# Sheet1.net
KiCad netlist of a schematic drawn in Altium Designer
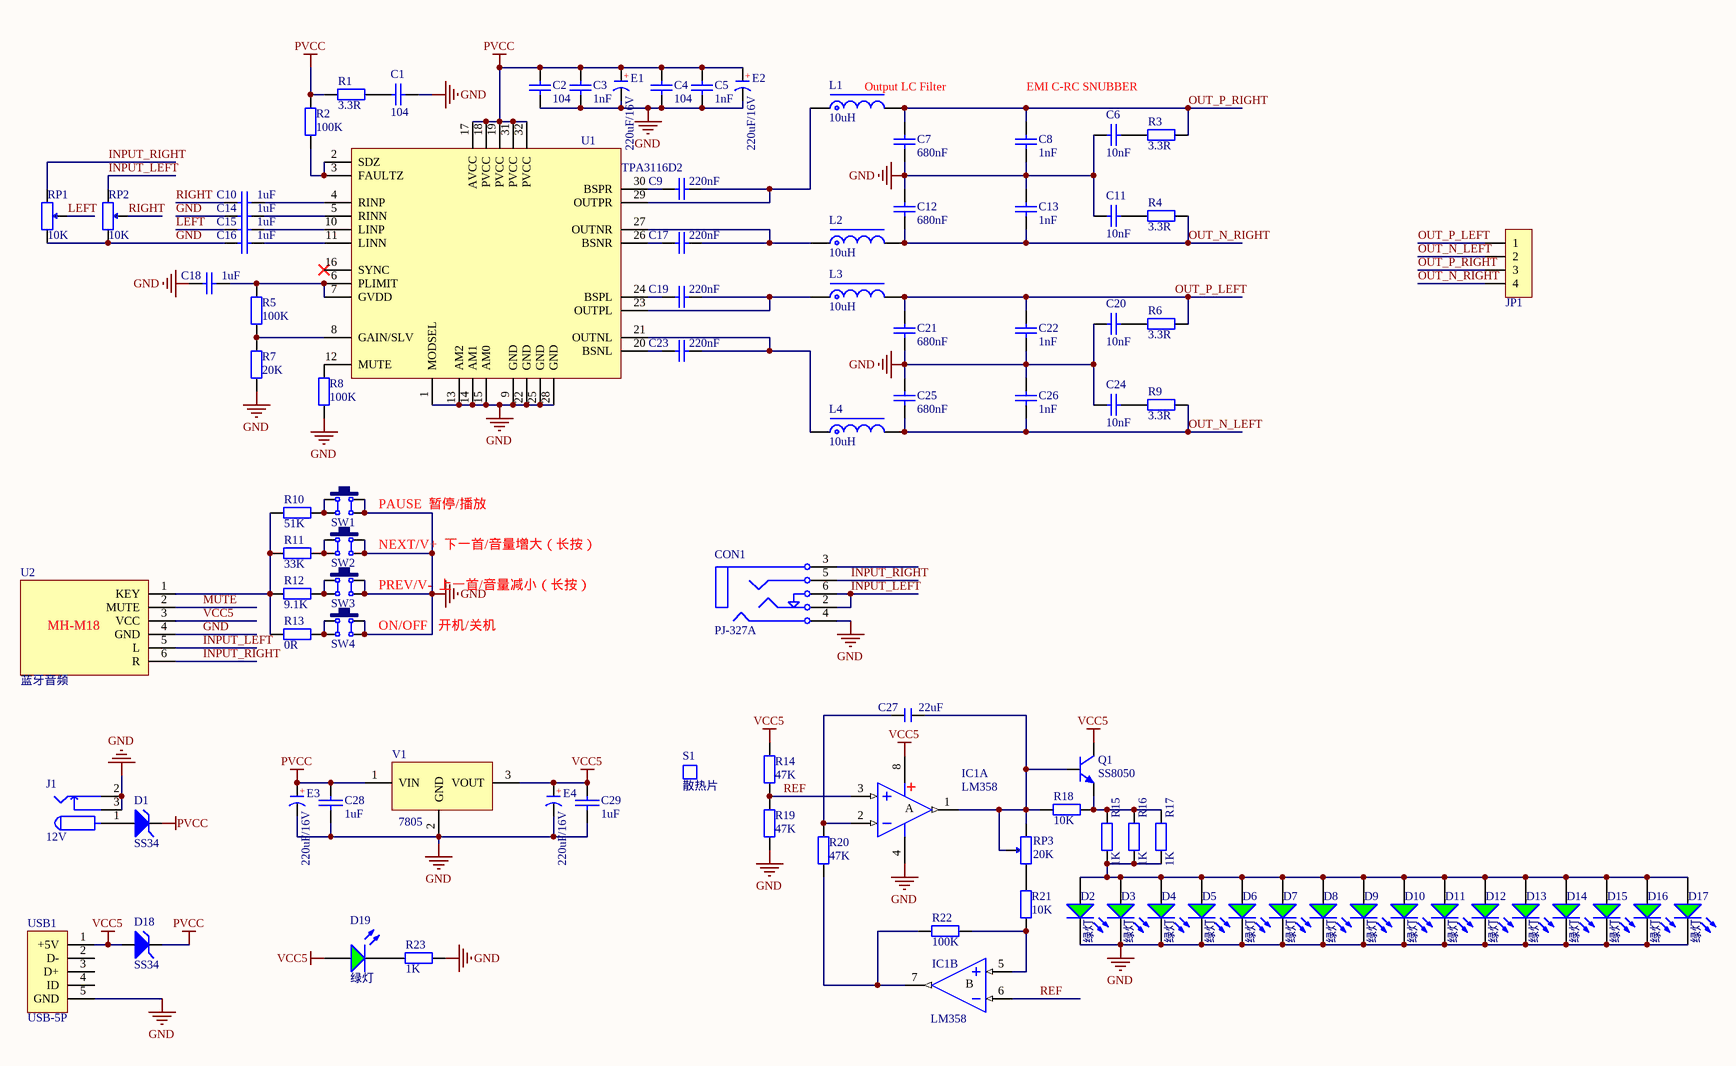
[diagram p0: Sheet1.SchDoc]

(export (version "E")
  (design (tool "Eeschema 10.0.6"))
  (components
    (comp (ref "C1")
      (value "104")
      (footprint "LC-0603_C")
      (description "贴片电容")
      (libsource (lib "Miscellaneous Devices LC") (part "0603 1nF (102) 10% 50V"))
    )
    (comp (ref "C2")
      (value "104")
      (footprint "LC-0603_C")
      (description "贴片电容")
      (libsource (lib "Miscellaneous Devices LC") (part "0603 1nF (102) 10% 50V"))
    )
    (comp (ref "C3")
      (value "1nF")
      (footprint "LC-0603_C")
      (description "贴片电容")
      (libsource (lib "Miscellaneous Devices LC") (part "0603 1nF (102) 10% 50V"))
    )
    (comp (ref "C4")
      (value "104")
      (footprint "LC-0603_C")
      (description "贴片电容")
      (libsource (lib "Miscellaneous Devices LC") (part "0603 1nF (102) 10% 50V"))
    )
    (comp (ref "C5")
      (value "1nF")
      (footprint "LC-0603_C")
      (description "贴片电容")
      (libsource (lib "Miscellaneous Devices LC") (part "0603 1nF (102) 10% 50V"))
    )
    (comp (ref "C6")
      (value "10nF")
      (footprint "LC-0603_C")
      (description "贴片电容")
      (libsource (lib "Miscellaneous Devices LC") (part "0603 1nF (102) 10% 50V"))
    )
    (comp (ref "C7")
      (value "680nF")
      (footprint "LC-0603_C")
      (description "贴片电容")
      (libsource (lib "Miscellaneous Devices LC") (part "0603 1nF (102) 10% 50V"))
    )
    (comp (ref "C8")
      (value "1nF")
      (footprint "LC-0603_C")
      (description "贴片电容")
      (libsource (lib "Miscellaneous Devices LC") (part "0603 1nF (102) 10% 50V"))
    )
    (comp (ref "C9")
      (value "220nF")
      (footprint "LC-0603_C")
      (description "贴片电容")
      (libsource (lib "Miscellaneous Devices LC") (part "0603 1nF (102) 10% 50V"))
    )
    (comp (ref "C10")
      (value "1uF")
      (footprint "LC-0603_C")
      (description "贴片电容")
      (libsource (lib "Miscellaneous Devices LC") (part "0603 1nF (102) 10% 50V"))
    )
    (comp (ref "C11")
      (value "10nF")
      (footprint "LC-0603_C")
      (description "贴片电容")
      (libsource (lib "Miscellaneous Devices LC") (part "0603 1nF (102) 10% 50V"))
    )
    (comp (ref "C12")
      (value "680nF")
      (footprint "LC-0603_C")
      (description "贴片电容")
      (libsource (lib "Miscellaneous Devices LC") (part "0603 1nF (102) 10% 50V"))
    )
    (comp (ref "C13")
      (value "1nF")
      (footprint "LC-0603_C")
      (description "贴片电容")
      (libsource (lib "Miscellaneous Devices LC") (part "0603 1nF (102) 10% 50V"))
    )
    (comp (ref "C14")
      (value "1uF")
      (footprint "LC-0603_C")
      (description "贴片电容")
      (libsource (lib "Miscellaneous Devices LC") (part "0603 1nF (102) 10% 50V"))
    )
    (comp (ref "C15")
      (value "1uF")
      (footprint "LC-0603_C")
      (description "贴片电容")
      (libsource (lib "Miscellaneous Devices LC") (part "0603 1nF (102) 10% 50V"))
    )
    (comp (ref "C16")
      (value "1uF")
      (footprint "LC-0603_C")
      (description "贴片电容")
      (libsource (lib "Miscellaneous Devices LC") (part "0603 1nF (102) 10% 50V"))
    )
    (comp (ref "C17")
      (value "220nF")
      (footprint "LC-0603_C")
      (description "贴片电容")
      (libsource (lib "Miscellaneous Devices LC") (part "0603 1nF (102) 10% 50V"))
    )
    (comp (ref "C18")
      (value "1uF")
      (footprint "LC-0603_C")
      (description "贴片电容")
      (libsource (lib "Miscellaneous Devices LC") (part "0603 1nF (102) 10% 50V"))
    )
    (comp (ref "C19")
      (value "220nF")
      (footprint "LC-0603_C")
      (description "贴片电容")
      (libsource (lib "Miscellaneous Devices LC") (part "0603 1nF (102) 10% 50V"))
    )
    (comp (ref "C20")
      (value "10nF")
      (footprint "LC-0603_C")
      (description "贴片电容")
      (libsource (lib "Miscellaneous Devices LC") (part "0603 1nF (102) 10% 50V"))
    )
    (comp (ref "C21")
      (value "680nF")
      (footprint "LC-0603_C")
      (description "贴片电容")
      (libsource (lib "Miscellaneous Devices LC") (part "0603 1nF (102) 10% 50V"))
    )
    (comp (ref "C22")
      (value "1nF")
      (footprint "LC-0603_C")
      (description "贴片电容")
      (libsource (lib "Miscellaneous Devices LC") (part "0603 1nF (102) 10% 50V"))
    )
    (comp (ref "C23")
      (value "220nF")
      (footprint "LC-0603_C")
      (description "贴片电容")
      (libsource (lib "Miscellaneous Devices LC") (part "0603 1nF (102) 10% 50V"))
    )
    (comp (ref "C24")
      (value "10nF")
      (footprint "LC-0603_C")
      (description "贴片电容")
      (libsource (lib "Miscellaneous Devices LC") (part "0603 1nF (102) 10% 50V"))
    )
    (comp (ref "C25")
      (value "680nF")
      (footprint "LC-0603_C")
      (description "贴片电容")
      (libsource (lib "Miscellaneous Devices LC") (part "0603 1nF (102) 10% 50V"))
    )
    (comp (ref "C26")
      (value "1nF")
      (footprint "LC-0603_C")
      (description "贴片电容")
      (libsource (lib "Miscellaneous Devices LC") (part "0603 1nF (102) 10% 50V"))
    )
    (comp (ref "C27")
      (value "22uF")
      (footprint "C 1210_M")
      (description "无极性贴片电容")
      (fields (field (name "版权归属") "源创客"))
      (libsource (lib "3.1   - 电阻-电容-电感") (part "C"))
    )
    (comp (ref "C28")
      (value "1uF")
      (footprint "LC-0603_C")
      (description "Capacitor 0805")
      (libsource (lib "CD's_LIB_2018") (part "0805C"))
    )
    (comp (ref "C29")
      (value "1uF")
      (footprint "LC-0603_C")
      (description "Capacitor 0805")
      (libsource (lib "CD's_LIB_2018") (part "0805C"))
    )
    (comp (ref "CON1")
      (value "PJ-327A")
      (footprint "PJ-327A")
      (description "3.5mm耳机插座")
      (libsource (lib "4.1   - 接口类") (part "PJ-327A"))
    )
    (comp (ref "D1")
      (value "SS34")
      (footprint "D1812")
      (description "Zener Diode")
      (libsource (lib "CD's_LIB_2018") (part "1N5822"))
    )
    (comp (ref "D2")
      (value "绿灯")
      (footprint "LC-0603_LED_S1")
      (description "发光二极管")
      (libsource (lib "Miscellaneous Devices LC") (part "绿灯"))
    )
    (comp (ref "D3")
      (value "绿灯")
      (footprint "LC-0603_LED_S1")
      (description "发光二极管")
      (libsource (lib "Miscellaneous Devices LC") (part "绿灯"))
    )
    (comp (ref "D4")
      (value "绿灯")
      (footprint "LC-0603_LED_S1")
      (description "发光二极管")
      (libsource (lib "Miscellaneous Devices LC") (part "绿灯"))
    )
    (comp (ref "D5")
      (value "绿灯")
      (footprint "LC-0603_LED_S1")
      (description "发光二极管")
      (libsource (lib "Miscellaneous Devices LC") (part "绿灯"))
    )
    (comp (ref "D6")
      (value "绿灯")
      (footprint "LC-0603_LED_S1")
      (description "发光二极管")
      (libsource (lib "Miscellaneous Devices LC") (part "绿灯"))
    )
    (comp (ref "D7")
      (value "绿灯")
      (footprint "LC-0603_LED_S1")
      (description "发光二极管")
      (libsource (lib "Miscellaneous Devices LC") (part "绿灯"))
    )
    (comp (ref "D8")
      (value "绿灯")
      (footprint "LC-0603_LED_S1")
      (description "发光二极管")
      (libsource (lib "Miscellaneous Devices LC") (part "绿灯"))
    )
    (comp (ref "D9")
      (value "绿灯")
      (footprint "LC-0603_LED_S1")
      (description "发光二极管")
      (libsource (lib "Miscellaneous Devices LC") (part "绿灯"))
    )
    (comp (ref "D10")
      (value "绿灯")
      (footprint "LC-0603_LED_S1")
      (description "发光二极管")
      (libsource (lib "Miscellaneous Devices LC") (part "绿灯"))
    )
    (comp (ref "D11")
      (value "绿灯")
      (footprint "LC-0603_LED_S1")
      (description "发光二极管")
      (libsource (lib "Miscellaneous Devices LC") (part "绿灯"))
    )
    (comp (ref "D12")
      (value "绿灯")
      (footprint "LC-0603_LED_S1")
      (description "发光二极管")
      (libsource (lib "Miscellaneous Devices LC") (part "绿灯"))
    )
    (comp (ref "D13")
      (value "绿灯")
      (footprint "LC-0603_LED_S1")
      (description "发光二极管")
      (libsource (lib "Miscellaneous Devices LC") (part "绿灯"))
    )
    (comp (ref "D14")
      (value "绿灯")
      (footprint "LC-0603_LED_S1")
      (description "发光二极管")
      (libsource (lib "Miscellaneous Devices LC") (part "绿灯"))
    )
    (comp (ref "D15")
      (value "绿灯")
      (footprint "LC-0603_LED_S1")
      (description "发光二极管")
      (libsource (lib "Miscellaneous Devices LC") (part "绿灯"))
    )
    (comp (ref "D16")
      (value "绿灯")
      (footprint "LC-0603_LED_S1")
      (description "发光二极管")
      (libsource (lib "Miscellaneous Devices LC") (part "绿灯"))
    )
    (comp (ref "D17")
      (value "绿灯")
      (footprint "LC-0603_LED_S1")
      (description "发光二极管")
      (libsource (lib "Miscellaneous Devices LC") (part "绿灯"))
    )
    (comp (ref "D18")
      (value "SS34")
      (footprint "D1812")
      (description "Zener Diode")
      (libsource (lib "CD's_LIB_2018") (part "1N5822"))
    )
    (comp (ref "D19")
      (value "绿灯")
      (footprint "LC-0603_LED_S1")
      (description "发光二极管")
      (libsource (lib "Miscellaneous Devices LC") (part "绿灯"))
    )
    (comp (ref "E1")
      (value "220uF/16V")
      (footprint "CAP 5.0*10*12.5 - BK")
      (description "直插电解电容")
      (fields (field (name "版权归属") "源创客"))
      (libsource (lib "3.1   - 电阻-电容-电感") (part "C-CAP"))
    )
    (comp (ref "E2")
      (value "220uF/16V")
      (footprint "CAP 5.0*10*12.5 - BK")
      (description "直插电解电容")
      (fields (field (name "版权归属") "源创客"))
      (libsource (lib "3.1   - 电阻-电容-电感") (part "C-CAP"))
    )
    (comp (ref "E3")
      (value "220uF/16V")
      (footprint "CAP 5.0*10*12.5 - BK")
      (description "直插电解电容")
      (fields (field (name "版权归属") "源创客"))
      (libsource (lib "3.1   - 电阻-电容-电感") (part "C-CAP"))
    )
    (comp (ref "E4")
      (value "220uF/16V")
      (footprint "CAP 5.0*10*12.5 - BK")
      (description "直插电解电容")
      (fields (field (name "版权归属") "源创客"))
      (libsource (lib "3.1   - 电阻-电容-电感") (part "C-CAP"))
    )
    (comp (ref "IC1")
      (value "LM358")
      (footprint "SOP8_M")
      (description "双路运放")
      (fields (field (name "版权归属") "源创客"))
      (libsource (lib "1.1   - IC芯片") (part "LM358"))
    )
    (comp (ref "J1") (value "12V") (footprint "DC10B") (libsource (lib "Explorer STM32F407封装库") (part "POW")))
    (comp (ref "JP1")
      (value "HDR-1X4")
      (footprint "KF128-5.08-4P")
      (description "4P接插件")
      (fields (field (name "版权归属") "源创客"))
      (libsource (lib "4.10 - 接插件-脚距5.08") (part "Header 4"))
    )
    (comp (ref "L1")
      (value "10uH")
      (footprint "CD105")
      (description "贴片功率电感")
      (fields (field (name "版权归属") "源创客"))
      (libsource (lib "3.1   - 电阻-电容-电感") (part "L-CD"))
    )
    (comp (ref "L2")
      (value "10uH")
      (footprint "CD105")
      (description "贴片功率电感")
      (fields (field (name "版权归属") "源创客"))
      (libsource (lib "3.1   - 电阻-电容-电感") (part "L-CD"))
    )
    (comp (ref "L3")
      (value "10uH")
      (footprint "CD105")
      (description "贴片功率电感")
      (fields (field (name "版权归属") "源创客"))
      (libsource (lib "3.1   - 电阻-电容-电感") (part "L-CD"))
    )
    (comp (ref "L4")
      (value "10uH")
      (footprint "CD105")
      (description "贴片功率电感")
      (fields (field (name "版权归属") "源创客"))
      (libsource (lib "3.1   - 电阻-电容-电感") (part "L-CD"))
    )
    (comp (ref "Q1")
      (value "SS8050")
      (footprint "SOT23-3L")
      (description "高频放大-NPN型")
      (fields (field (name "版权归属") "源创客"))
      (libsource (lib "6.2   - 三极管") (part "8050-SMD"))
    )
    (comp (ref "R1")
      (value "3.3R")
      (footprint "LC-0603_R")
      (description "贴片电阻")
      (libsource (lib "") (part "0603 1Ω (1R00) 1%_1"))
    )
    (comp (ref "R2")
      (value "100K")
      (footprint "LC-0603_R")
      (description "贴片电阻")
      (libsource (lib "Miscellaneous Devices LC") (part "0603 1Ω (1R00) 1%"))
    )
    (comp (ref "R3")
      (value "3.3R")
      (footprint "LC-0603_R")
      (description "贴片电阻")
      (libsource (lib "") (part "0603 1Ω (1R00) 1%_1"))
    )
    (comp (ref "R4")
      (value "3.3R")
      (footprint "LC-0603_R")
      (description "贴片电阻")
      (libsource (lib "Miscellaneous Devices LC") (part "0603 1Ω (1R00) 1%"))
    )
    (comp (ref "R5")
      (value "100K")
      (footprint "LC-0603_R")
      (description "贴片电阻")
      (libsource (lib "Miscellaneous Devices LC") (part "0603 1Ω (1R00) 1%"))
    )
    (comp (ref "R6")
      (value "3.3R")
      (footprint "LC-0603_R")
      (description "贴片电阻")
      (libsource (lib "") (part "0603 1Ω (1R00) 1%_1"))
    )
    (comp (ref "R7")
      (value "20K")
      (footprint "LC-0603_R")
      (description "贴片电阻")
      (libsource (lib "Miscellaneous Devices LC") (part "0603 1Ω (1R00) 1%"))
    )
    (comp (ref "R8")
      (value "100K")
      (footprint "LC-0603_R")
      (description "贴片电阻")
      (libsource (lib "Miscellaneous Devices LC") (part "0603 1Ω (1R00) 1%"))
    )
    (comp (ref "R9")
      (value "3.3R")
      (footprint "LC-0603_R")
      (description "贴片电阻")
      (libsource (lib "Miscellaneous Devices LC") (part "0603 1Ω (1R00) 1%"))
    )
    (comp (ref "R10")
      (value "51K")
      (footprint "LC-0603_R")
      (description "贴片电阻")
      (libsource (lib "") (part "0603 1Ω (1R00) 1%_2"))
    )
    (comp (ref "R11")
      (value "33K")
      (footprint "LC-0603_R")
      (description "贴片电阻")
      (libsource (lib "") (part "0603 1Ω (1R00) 1%_2"))
    )
    (comp (ref "R12")
      (value "9.1K")
      (footprint "LC-0603_R")
      (description "贴片电阻")
      (libsource (lib "") (part "0603 1Ω (1R00) 1%_2"))
    )
    (comp (ref "R13")
      (value "0R")
      (footprint "LC-0603_R")
      (description "贴片电阻")
      (libsource (lib "") (part "0603 1Ω (1R00) 1%_2"))
    )
    (comp (ref "R14")
      (value "47K")
      (footprint "LC-0603_R")
      (description "贴片电阻")
      (fields (field (name "PUBLISHER") "Altium Limited"))
      (libsource (lib "liu_2016") (part "Res1"))
    )
    (comp (ref "R15")
      (value "1K")
      (footprint "LC-0603_R")
      (description "贴片电阻")
      (fields (field (name "PUBLISHER") "Altium Limited"))
      (libsource (lib "liu_2016") (part "Res1"))
    )
    (comp (ref "R16")
      (value "1K")
      (footprint "LC-0603_R")
      (description "贴片电阻")
      (fields (field (name "PUBLISHER") "Altium Limited"))
      (libsource (lib "liu_2016") (part "Res1"))
    )
    (comp (ref "R17")
      (value "1K")
      (footprint "LC-0603_R")
      (description "贴片电阻")
      (fields (field (name "PUBLISHER") "Altium Limited"))
      (libsource (lib "liu_2016") (part "Res1"))
    )
    (comp (ref "R18")
      (value "10K")
      (footprint "LC-0603_R")
      (description "贴片电阻")
      (fields (field (name "PUBLISHER") "Altium Limited"))
      (libsource (lib "") (part "Res1_1"))
    )
    (comp (ref "R19")
      (value "47K")
      (footprint "LC-0603_R")
      (description "贴片电阻")
      (fields (field (name "PUBLISHER") "Altium Limited"))
      (libsource (lib "liu_2016") (part "Res1"))
    )
    (comp (ref "R20")
      (value "47K")
      (footprint "LC-0603_R")
      (description "贴片电阻")
      (fields (field (name "PUBLISHER") "Altium Limited"))
      (libsource (lib "liu_2016") (part "Res1"))
    )
    (comp (ref "R21")
      (value "10K")
      (footprint "LC-0603_R")
      (description "贴片电阻")
      (fields (field (name "PUBLISHER") "Altium Limited"))
      (libsource (lib "liu_2016") (part "Res1"))
    )
    (comp (ref "R22")
      (value "100K")
      (footprint "LC-0603_R")
      (description "贴片电阻")
      (fields (field (name "PUBLISHER") "Altium Limited"))
      (libsource (lib "") (part "Res1_1"))
    )
    (comp (ref "R23")
      (value "1K")
      (footprint "LC-0603_R")
      (description "贴片电阻")
      (fields (field (name "PUBLISHER") "Altium Limited"))
      (libsource (lib "") (part "Res1_1"))
    )
    (comp (ref "RP1")
      (value "10K")
      (footprint "RV0931")
      (description "插件单联电位器")
      (fields (field (name "版权归属") "源创客"))
      (libsource (lib "3.1   - 电阻-电容-电感") (part "RP-ID"))
    )
    (comp (ref "RP2")
      (value "10K")
      (footprint "RV0931")
      (description "插件单联电位器")
      (fields (field (name "版权归属") "源创客"))
      (libsource (lib "3.1   - 电阻-电容-电感") (part "RP-ID"))
    )
    (comp (ref "RP3")
      (value "20K")
      (footprint "RM065")
      (description "插件单联电位器")
      (fields (field (name "版权归属") "源创客"))
      (libsource (lib "3.1   - 电阻-电容-电感") (part "RP-ID"))
    )
    (comp (ref "S1")
      (value "散热片")
      (footprint "SRP10-15-21-P")
      (fields (field (name "版权归属") "源创客"))
      (libsource (lib "15.1 - 未分类器件") (part "S1"))
    )
    (comp (ref "SW1")
      (value "6x6x5")
      (footprint "TSW DIP-6*6*12")
      (description "直插6x6轻触开关")
      (fields (field (name "版权归属") "源创客"))
      (libsource (lib "5.1   - 按键-开关") (part "TSW DIP-6x6"))
    )
    (comp (ref "SW2")
      (value "6x6x5")
      (footprint "TSW DIP-6*6*12")
      (description "直插6x6轻触开关")
      (fields (field (name "版权归属") "源创客"))
      (libsource (lib "5.1   - 按键-开关") (part "TSW DIP-6x6"))
    )
    (comp (ref "SW3")
      (value "6x6x5")
      (footprint "TSW DIP-6*6*12")
      (description "直插6x6轻触开关")
      (fields (field (name "版权归属") "源创客"))
      (libsource (lib "5.1   - 按键-开关") (part "TSW DIP-6x6"))
    )
    (comp (ref "SW4")
      (value "6x6x5")
      (footprint "TSW DIP-6*6*12")
      (description "直插6x6轻触开关")
      (fields (field (name "版权归属") "源创客"))
      (libsource (lib "5.1   - 按键-开关") (part "TSW DIP-6x6"))
    )
    (comp (ref "U1")
      (value "TPA3116D2")
      (footprint "HTSSOP-32")
      (libsource (lib "SWUST_PanPan") (part "TPA3116D2"))
    )
    (comp (ref "U2") (value "蓝牙音频") (footprint "MH-M18蓝牙模块") (libsource (lib "13.1 - 模块") (part "蓝牙音频接收器模块")))
    (comp (ref "USB1")
      (value "USB-5P")
      (footprint "USB-MICRO_A")
      (description "微型USB母座")
      (fields (field (name "版权归属") "源创客"))
      (libsource (lib "4.1   - 接口类") (part "USB-5P"))
    )
    (comp (ref "V1")
      (value "7805")
      (footprint "TO220A")
      (description "线性稳压芯片")
      (fields (field (name "版权归属") "源创客"))
      (libsource (lib "1.3   - 电源类芯片") (part "78xx"))
    )
  )
  (nets
    (net (code "1") (name "/INPUT_LEFT") (class "Default")
      (node (ref "CON1") (pin "2") (pinfunction "2_2") (pintype "passive"))
      (node (ref "CON1") (pin "6") (pinfunction "6_6") (pintype "passive"))
      (node (ref "RP2") (pin "1") (pinfunction "1_1") (pintype "passive"))
      (node (ref "U2") (pin "5") (pinfunction "L_5") (pintype "passive"))
    )
    (net (code "2") (name "/INPUT_RIGHT") (class "Default")
      (node (ref "CON1") (pin "5") (pinfunction "5_5") (pintype "passive"))
      (node (ref "RP1") (pin "1") (pinfunction "1_1") (pintype "passive"))
      (node (ref "U2") (pin "6") (pinfunction "R_6") (pintype "passive"))
    )
    (net (code "3") (name "/LEFT") (class "Default")
      (node (ref "C15") (pin "1") (pinfunction "1_1") (pintype "passive"))
      (node (ref "RP1") (pin "2") (pinfunction "2_2") (pintype "passive"))
    )
    (net (code "4") (name "/MUTE") (class "Default")
      (node (ref "U2") (pin "2") (pinfunction "MUTE_2") (pintype "passive"))
    )
    (net (code "5") (name "/OUT_N_LEFT") (class "Default")
      (node (ref "C25") (pin "2") (pinfunction "2_2") (pintype "passive"))
      (node (ref "C26") (pin "2") (pinfunction "2_2") (pintype "passive"))
      (node (ref "JP1") (pin "2") (pinfunction "2_2") (pintype "passive"))
      (node (ref "L4") (pin "2") (pinfunction "2_2") (pintype "passive"))
      (node (ref "R9") (pin "2") (pinfunction "2_2") (pintype "passive"))
    )
    (net (code "6") (name "/OUT_N_RIGHT") (class "Default")
      (node (ref "C12") (pin "2") (pinfunction "2_2") (pintype "passive"))
      (node (ref "C13") (pin "2") (pinfunction "2_2") (pintype "passive"))
      (node (ref "JP1") (pin "4") (pinfunction "4_4") (pintype "passive"))
      (node (ref "L2") (pin "2") (pinfunction "2_2") (pintype "passive"))
      (node (ref "R4") (pin "2") (pinfunction "2_2") (pintype "passive"))
    )
    (net (code "7") (name "/OUT_P_LEFT") (class "Default")
      (node (ref "C21") (pin "1") (pinfunction "1_1") (pintype "passive"))
      (node (ref "C22") (pin "1") (pinfunction "1_1") (pintype "passive"))
      (node (ref "JP1") (pin "1") (pinfunction "1_1") (pintype "passive"))
      (node (ref "L3") (pin "2") (pinfunction "2_2") (pintype "passive"))
      (node (ref "R6") (pin "2") (pinfunction "2_2") (pintype "passive"))
    )
    (net (code "8") (name "/OUT_P_RIGHT") (class "Default")
      (node (ref "C7") (pin "1") (pinfunction "1_1") (pintype "passive"))
      (node (ref "C8") (pin "1") (pinfunction "1_1") (pintype "passive"))
      (node (ref "JP1") (pin "3") (pinfunction "3_3") (pintype "passive"))
      (node (ref "L1") (pin "2") (pinfunction "2_2") (pintype "passive"))
      (node (ref "R3") (pin "2") (pinfunction "2_2") (pintype "passive"))
    )
    (net (code "9") (name "/REF") (class "Default")
      (node (ref "IC1") (pin "3") (pinfunction "IN+_3") (pintype "input"))
      (node (ref "IC1") (pin "6") (pinfunction "IN-_6") (pintype "input"))
      (node (ref "R14") (pin "2") (pinfunction "2_2") (pintype "passive"))
      (node (ref "R19") (pin "1") (pinfunction "1_1") (pintype "passive"))
    )
    (net (code "10") (name "/RIGHT") (class "Default")
      (node (ref "C10") (pin "1") (pinfunction "1_1") (pintype "passive"))
      (node (ref "RP2") (pin "2") (pinfunction "2_2") (pintype "passive"))
    )
    (net (code "11") (name "GND") (class "Default")
      (node (ref "C1") (pin "2") (pinfunction "2_2") (pintype "passive"))
      (node (ref "C11") (pin "1") (pinfunction "1_1") (pintype "passive"))
      (node (ref "C12") (pin "1") (pinfunction "1_1") (pintype "passive"))
      (node (ref "C13") (pin "1") (pinfunction "1_1") (pintype "passive"))
      (node (ref "C14") (pin "1") (pinfunction "1_1") (pintype "passive"))
      (node (ref "C16") (pin "1") (pinfunction "1_1") (pintype "passive"))
      (node (ref "C18") (pin "1") (pinfunction "1_1") (pintype "passive"))
      (node (ref "C2") (pin "2") (pinfunction "2_2") (pintype "passive"))
      (node (ref "C20") (pin "1") (pinfunction "1_1") (pintype "passive"))
      (node (ref "C21") (pin "2") (pinfunction "2_2") (pintype "passive"))
      (node (ref "C22") (pin "2") (pinfunction "2_2") (pintype "passive"))
      (node (ref "C24") (pin "1") (pinfunction "1_1") (pintype "passive"))
      (node (ref "C25") (pin "1") (pinfunction "1_1") (pintype "passive"))
      (node (ref "C26") (pin "1") (pinfunction "1_1") (pintype "passive"))
      (node (ref "C28") (pin "1") (pinfunction "1_1") (pintype "passive"))
      (node (ref "C29") (pin "1") (pinfunction "1_1") (pintype "passive"))
      (node (ref "C3") (pin "2") (pinfunction "2_2") (pintype "passive"))
      (node (ref "C4") (pin "2") (pinfunction "2_2") (pintype "passive"))
      (node (ref "C5") (pin "2") (pinfunction "2_2") (pintype "passive"))
      (node (ref "C6") (pin "1") (pinfunction "1_1") (pintype "passive"))
      (node (ref "C7") (pin "2") (pinfunction "2_2") (pintype "passive"))
      (node (ref "C8") (pin "2") (pinfunction "2_2") (pintype "passive"))
      (node (ref "CON1") (pin "4") (pinfunction "4_4") (pintype "passive"))
      (node (ref "D10") (pin "K") (pinfunction "K_K") (pintype "passive"))
      (node (ref "D11") (pin "K") (pinfunction "K_K") (pintype "passive"))
      (node (ref "D12") (pin "K") (pinfunction "K_K") (pintype "passive"))
      (node (ref "D13") (pin "K") (pinfunction "K_K") (pintype "passive"))
      (node (ref "D14") (pin "K") (pinfunction "K_K") (pintype "passive"))
      (node (ref "D15") (pin "K") (pinfunction "K_K") (pintype "passive"))
      (node (ref "D16") (pin "K") (pinfunction "K_K") (pintype "passive"))
      (node (ref "D17") (pin "K") (pinfunction "K_K") (pintype "passive"))
      (node (ref "D2") (pin "K") (pinfunction "K_K") (pintype "passive"))
      (node (ref "D3") (pin "K") (pinfunction "K_K") (pintype "passive"))
      (node (ref "D4") (pin "K") (pinfunction "K_K") (pintype "passive"))
      (node (ref "D5") (pin "K") (pinfunction "K_K") (pintype "passive"))
      (node (ref "D6") (pin "K") (pinfunction "K_K") (pintype "passive"))
      (node (ref "D7") (pin "K") (pinfunction "K_K") (pintype "passive"))
      (node (ref "D8") (pin "K") (pinfunction "K_K") (pintype "passive"))
      (node (ref "D9") (pin "K") (pinfunction "K_K") (pintype "passive"))
      (node (ref "E1") (pin "2") (pinfunction "K_2") (pintype "passive"))
      (node (ref "E2") (pin "2") (pinfunction "K_2") (pintype "passive"))
      (node (ref "E3") (pin "2") (pinfunction "K_2") (pintype "passive"))
      (node (ref "E4") (pin "2") (pinfunction "K_2") (pintype "passive"))
      (node (ref "IC1") (pin "4") (pinfunction "V-_4") (pintype "power_in"))
      (node (ref "J1") (pin "2") (pintype "passive"))
      (node (ref "J1") (pin "3") (pintype "passive"))
      (node (ref "R19") (pin "2") (pinfunction "2_2") (pintype "passive"))
      (node (ref "R23") (pin "2") (pinfunction "2_2") (pintype "passive"))
      (node (ref "R7") (pin "1") (pinfunction "1_1") (pintype "passive"))
      (node (ref "R8") (pin "1") (pinfunction "1_1") (pintype "passive"))
      (node (ref "RP1") (pin "3") (pinfunction "3_3") (pintype "passive"))
      (node (ref "RP2") (pin "3") (pinfunction "3_3") (pintype "passive"))
      (node (ref "SW1") (pin "2") (pinfunction "2_2") (pintype "passive"))
      (node (ref "SW1") (pin "3") (pinfunction "3_3") (pintype "passive"))
      (node (ref "SW2") (pin "2") (pinfunction "2_2") (pintype "passive"))
      (node (ref "SW2") (pin "3") (pinfunction "3_3") (pintype "passive"))
      (node (ref "SW3") (pin "2") (pinfunction "2_2") (pintype "passive"))
      (node (ref "SW3") (pin "3") (pinfunction "3_3") (pintype "passive"))
      (node (ref "SW4") (pin "2") (pinfunction "2_2") (pintype "passive"))
      (node (ref "SW4") (pin "3") (pinfunction "3_3") (pintype "passive"))
      (node (ref "U1") (pin "1") (pinfunction "MODSEL_1") (pintype "passive"))
      (node (ref "U1") (pin "13") (pinfunction "AM2_13") (pintype "passive"))
      (node (ref "U1") (pin "14") (pinfunction "AM1_14") (pintype "passive"))
      (node (ref "U1") (pin "15") (pinfunction "AM0_15") (pintype "passive"))
      (node (ref "U1") (pin "22") (pinfunction "GND_22") (pintype "passive"))
      (node (ref "U1") (pin "25") (pinfunction "GND_25") (pintype "passive"))
      (node (ref "U1") (pin "28") (pinfunction "GND_28") (pintype "passive"))
      (node (ref "U1") (pin "9") (pinfunction "GND_9") (pintype "passive"))
      (node (ref "U2") (pin "4") (pinfunction "GND_4") (pintype "passive"))
      (node (ref "USB1") (pin "5") (pinfunction "GND_5") (pintype "passive"))
      (node (ref "V1") (pin "2") (pinfunction "GND_2") (pintype "passive"))
    )
    (net (code "12") (name "Net-(C1-Pad1)") (class "Default")
      (node (ref "C1") (pin "1") (pinfunction "1_1") (pintype "passive"))
      (node (ref "R1") (pin "2") (pinfunction "2_2") (pintype "passive"))
    )
    (net (code "13") (name "Net-(C6-Pad2)") (class "Default")
      (node (ref "C6") (pin "2") (pinfunction "2_2") (pintype "passive"))
      (node (ref "R3") (pin "1") (pinfunction "1_1") (pintype "passive"))
    )
    (net (code "14") (name "Net-(C11-Pad2)") (class "Default")
      (node (ref "C11") (pin "2") (pinfunction "2_2") (pintype "passive"))
      (node (ref "R4") (pin "1") (pinfunction "1_1") (pintype "passive"))
    )
    (net (code "15") (name "Net-(C20-Pad2)") (class "Default")
      (node (ref "C20") (pin "2") (pinfunction "2_2") (pintype "passive"))
      (node (ref "R6") (pin "1") (pinfunction "1_1") (pintype "passive"))
    )
    (net (code "16") (name "Net-(C24-Pad2)") (class "Default")
      (node (ref "C24") (pin "2") (pinfunction "2_2") (pintype "passive"))
      (node (ref "R9") (pin "1") (pinfunction "1_1") (pintype "passive"))
    )
    (net (code "17") (name "Net-(D1-A)") (class "Default")
      (node (ref "D1") (pin "1") (pinfunction "A_1") (pintype "passive"))
      (node (ref "J1") (pin "1") (pintype "passive"))
    )
    (net (code "18") (name "Net-(D10-PadA)") (class "Default")
      (node (ref "D10") (pin "A") (pinfunction "A_A") (pintype "passive"))
      (node (ref "D11") (pin "A") (pinfunction "A_A") (pintype "passive"))
      (node (ref "D12") (pin "A") (pinfunction "A_A") (pintype "passive"))
      (node (ref "D13") (pin "A") (pinfunction "A_A") (pintype "passive"))
      (node (ref "D14") (pin "A") (pinfunction "A_A") (pintype "passive"))
      (node (ref "D15") (pin "A") (pinfunction "A_A") (pintype "passive"))
      (node (ref "D16") (pin "A") (pinfunction "A_A") (pintype "passive"))
      (node (ref "D17") (pin "A") (pinfunction "A_A") (pintype "passive"))
      (node (ref "D2") (pin "A") (pinfunction "A_A") (pintype "passive"))
      (node (ref "D3") (pin "A") (pinfunction "A_A") (pintype "passive"))
      (node (ref "D4") (pin "A") (pinfunction "A_A") (pintype "passive"))
      (node (ref "D5") (pin "A") (pinfunction "A_A") (pintype "passive"))
      (node (ref "D6") (pin "A") (pinfunction "A_A") (pintype "passive"))
      (node (ref "D7") (pin "A") (pinfunction "A_A") (pintype "passive"))
      (node (ref "D8") (pin "A") (pinfunction "A_A") (pintype "passive"))
      (node (ref "D9") (pin "A") (pinfunction "A_A") (pintype "passive"))
      (node (ref "R15") (pin "2") (pinfunction "2_2") (pintype "passive"))
      (node (ref "R16") (pin "2") (pinfunction "2_2") (pintype "passive"))
      (node (ref "R17") (pin "2") (pinfunction "2_2") (pintype "passive"))
    )
    (net (code "19") (name "Net-(D19-PadK)") (class "Default")
      (node (ref "D19") (pin "K") (pinfunction "K_K") (pintype "passive"))
      (node (ref "R23") (pin "1") (pinfunction "1_1") (pintype "passive"))
    )
    (net (code "20") (name "Net-(IC1A-IN-)") (class "Default")
      (node (ref "C27") (pin "1") (pinfunction "1_1") (pintype "passive"))
      (node (ref "IC1") (pin "2") (pinfunction "IN-_2") (pintype "input"))
      (node (ref "R20") (pin "1") (pinfunction "1_1") (pintype "passive"))
    )
    (net (code "21") (name "Net-(IC1A-OUT)") (class "Default")
      (node (ref "C27") (pin "2") (pinfunction "2_2") (pintype "passive"))
      (node (ref "IC1") (pin "1") (pinfunction "OUT_1") (pintype "output"))
      (node (ref "Q1") (pin "1") (pinfunction "B_1") (pintype "passive"))
      (node (ref "R18") (pin "1") (pinfunction "1_1") (pintype "passive"))
      (node (ref "RP3") (pin "2") (pinfunction "2_2") (pintype "passive"))
      (node (ref "RP3") (pin "3") (pinfunction "3_3") (pintype "passive"))
    )
    (net (code "22") (name "Net-(IC1B-IN+)") (class "Default")
      (node (ref "IC1") (pin "5") (pinfunction "IN+_5") (pintype "input"))
      (node (ref "R21") (pin "2") (pinfunction "2_2") (pintype "passive"))
      (node (ref "R22") (pin "2") (pinfunction "2_2") (pintype "passive"))
    )
    (net (code "23") (name "Net-(IC1B-OUT)") (class "Default")
      (node (ref "IC1") (pin "7") (pinfunction "OUT_7") (pintype "output"))
      (node (ref "R20") (pin "2") (pinfunction "2_2") (pintype "passive"))
      (node (ref "R22") (pin "1") (pinfunction "1_1") (pintype "passive"))
    )
    (net (code "24") (name "Net-(Q1-E)") (class "Default")
      (node (ref "Q1") (pin "2") (pinfunction "E_2") (pintype "passive"))
      (node (ref "R15") (pin "1") (pinfunction "1_1") (pintype "passive"))
      (node (ref "R16") (pin "1") (pinfunction "1_1") (pintype "passive"))
      (node (ref "R17") (pin "1") (pinfunction "1_1") (pintype "passive"))
      (node (ref "R18") (pin "2") (pinfunction "2_2") (pintype "passive"))
    )
    (net (code "25") (name "Net-(R10-Pad1)") (class "Default")
      (node (ref "R10") (pin "1") (pinfunction "1_1") (pintype "passive"))
      (node (ref "SW1") (pin "1") (pinfunction "1_1") (pintype "passive"))
      (node (ref "SW1") (pin "4") (pinfunction "4_4") (pintype "passive"))
    )
    (net (code "26") (name "Net-(R11-Pad1)") (class "Default")
      (node (ref "R11") (pin "1") (pinfunction "1_1") (pintype "passive"))
      (node (ref "SW2") (pin "1") (pinfunction "1_1") (pintype "passive"))
      (node (ref "SW2") (pin "4") (pinfunction "4_4") (pintype "passive"))
    )
    (net (code "27") (name "Net-(R12-Pad1)") (class "Default")
      (node (ref "R12") (pin "1") (pinfunction "1_1") (pintype "passive"))
      (node (ref "SW3") (pin "1") (pinfunction "1_1") (pintype "passive"))
      (node (ref "SW3") (pin "4") (pinfunction "4_4") (pintype "passive"))
    )
    (net (code "28") (name "Net-(R13-Pad1)") (class "Default")
      (node (ref "R13") (pin "1") (pinfunction "1_1") (pintype "passive"))
      (node (ref "SW4") (pin "1") (pinfunction "1_1") (pintype "passive"))
      (node (ref "SW4") (pin "4") (pinfunction "4_4") (pintype "passive"))
    )
    (net (code "29") (name "Net-(R21-Pad1)") (class "Default")
      (node (ref "R21") (pin "1") (pinfunction "1_1") (pintype "passive"))
      (node (ref "RP3") (pin "1") (pinfunction "1_1") (pintype "passive"))
    )
    (net (code "30") (name "Net-(U1-BSNL)") (class "Default")
      (node (ref "C23") (pin "1") (pinfunction "1_1") (pintype "passive"))
      (node (ref "U1") (pin "20") (pinfunction "BSNL_20") (pintype "passive"))
    )
    (net (code "31") (name "Net-(U1-BSNR)") (class "Default")
      (node (ref "C17") (pin "1") (pinfunction "1_1") (pintype "passive"))
      (node (ref "U1") (pin "26") (pinfunction "BSNR_26") (pintype "passive"))
    )
    (net (code "32") (name "Net-(U1-BSPL)") (class "Default")
      (node (ref "C19") (pin "1") (pinfunction "1_1") (pintype "passive"))
      (node (ref "U1") (pin "24") (pinfunction "BSPL_24") (pintype "passive"))
    )
    (net (code "33") (name "Net-(U1-BSPR)") (class "Default")
      (node (ref "C9") (pin "1") (pinfunction "1_1") (pintype "passive"))
      (node (ref "U1") (pin "30") (pinfunction "BSPR_30") (pintype "passive"))
    )
    (net (code "34") (name "Net-(U1-FAULTZ)") (class "Default")
      (node (ref "R2") (pin "1") (pinfunction "1_1") (pintype "passive"))
      (node (ref "U1") (pin "2") (pinfunction "SDZ_2") (pintype "passive"))
      (node (ref "U1") (pin "3") (pinfunction "FAULTZ_3") (pintype "passive"))
    )
    (net (code "35") (name "Net-(U1-GAIN{slash}SLV)") (class "Default")
      (node (ref "R5") (pin "1") (pinfunction "1_1") (pintype "passive"))
      (node (ref "R7") (pin "2") (pinfunction "2_2") (pintype "passive"))
      (node (ref "U1") (pin "8") (pinfunction "GAIN/SLV_8") (pintype "passive"))
    )
    (net (code "36") (name "Net-(U1-GVDD)") (class "Default")
      (node (ref "C18") (pin "2") (pinfunction "2_2") (pintype "passive"))
      (node (ref "R5") (pin "2") (pinfunction "2_2") (pintype "passive"))
      (node (ref "U1") (pin "6") (pinfunction "PLIMIT_6") (pintype "passive"))
      (node (ref "U1") (pin "7") (pinfunction "GVDD_7") (pintype "passive"))
    )
    (net (code "37") (name "Net-(U1-LINN)") (class "Default")
      (node (ref "C16") (pin "2") (pinfunction "2_2") (pintype "passive"))
      (node (ref "U1") (pin "11") (pinfunction "LINN_11") (pintype "passive"))
    )
    (net (code "38") (name "Net-(U1-LINP)") (class "Default")
      (node (ref "C15") (pin "2") (pinfunction "2_2") (pintype "passive"))
      (node (ref "U1") (pin "10") (pinfunction "LINP_10") (pintype "passive"))
    )
    (net (code "39") (name "Net-(U1-MUTE)") (class "Default")
      (node (ref "R8") (pin "2") (pinfunction "2_2") (pintype "passive"))
      (node (ref "U1") (pin "12") (pinfunction "MUTE_12") (pintype "passive"))
    )
    (net (code "40") (name "Net-(U1-OUTNL)") (class "Default")
      (node (ref "C23") (pin "2") (pinfunction "2_2") (pintype "passive"))
      (node (ref "L4") (pin "1") (pinfunction "1_1") (pintype "passive"))
      (node (ref "U1") (pin "21") (pinfunction "OUTNL_21") (pintype "passive"))
    )
    (net (code "41") (name "Net-(U1-OUTNR)") (class "Default")
      (node (ref "C17") (pin "2") (pinfunction "2_2") (pintype "passive"))
      (node (ref "L2") (pin "1") (pinfunction "1_1") (pintype "passive"))
      (node (ref "U1") (pin "27") (pinfunction "OUTNR_27") (pintype "passive"))
    )
    (net (code "42") (name "Net-(U1-OUTPL)") (class "Default")
      (node (ref "C19") (pin "2") (pinfunction "2_2") (pintype "passive"))
      (node (ref "L3") (pin "1") (pinfunction "1_1") (pintype "passive"))
      (node (ref "U1") (pin "23") (pinfunction "OUTPL_23") (pintype "passive"))
    )
    (net (code "43") (name "Net-(U1-OUTPR)") (class "Default")
      (node (ref "C9") (pin "2") (pinfunction "2_2") (pintype "passive"))
      (node (ref "L1") (pin "1") (pinfunction "1_1") (pintype "passive"))
      (node (ref "U1") (pin "29") (pinfunction "OUTPR_29") (pintype "passive"))
    )
    (net (code "44") (name "Net-(U1-RINN)") (class "Default")
      (node (ref "C14") (pin "2") (pinfunction "2_2") (pintype "passive"))
      (node (ref "U1") (pin "5") (pinfunction "RINN_5") (pintype "passive"))
    )
    (net (code "45") (name "Net-(U1-RINP)") (class "Default")
      (node (ref "C10") (pin "2") (pinfunction "2_2") (pintype "passive"))
      (node (ref "U1") (pin "4") (pinfunction "RINP_4") (pintype "passive"))
    )
    (net (code "46") (name "Net-(U2-KEY)") (class "Default")
      (node (ref "R10") (pin "2") (pinfunction "2_2") (pintype "passive"))
      (node (ref "R11") (pin "2") (pinfunction "2_2") (pintype "passive"))
      (node (ref "R12") (pin "2") (pinfunction "2_2") (pintype "passive"))
      (node (ref "R13") (pin "2") (pinfunction "2_2") (pintype "passive"))
      (node (ref "U2") (pin "1") (pinfunction "KEY_1") (pintype "passive"))
    )
    (net (code "47") (name "PVCC") (class "Default")
      (node (ref "C2") (pin "1") (pinfunction "1_1") (pintype "passive"))
      (node (ref "C28") (pin "2") (pinfunction "2_2") (pintype "passive"))
      (node (ref "C3") (pin "1") (pinfunction "1_1") (pintype "passive"))
      (node (ref "C4") (pin "1") (pinfunction "1_1") (pintype "passive"))
      (node (ref "C5") (pin "1") (pinfunction "1_1") (pintype "passive"))
      (node (ref "D1") (pin "2") (pinfunction "K_2") (pintype "passive"))
      (node (ref "D18") (pin "2") (pinfunction "K_2") (pintype "passive"))
      (node (ref "E1") (pin "1") (pinfunction "A_1") (pintype "passive"))
      (node (ref "E2") (pin "1") (pinfunction "A_1") (pintype "passive"))
      (node (ref "E3") (pin "1") (pinfunction "A_1") (pintype "passive"))
      (node (ref "R1") (pin "1") (pinfunction "1_1") (pintype "passive"))
      (node (ref "R2") (pin "2") (pinfunction "2_2") (pintype "passive"))
      (node (ref "U1") (pin "17") (pinfunction "AVCC_17") (pintype "passive"))
      (node (ref "U1") (pin "18") (pinfunction "PVCC_18") (pintype "passive"))
      (node (ref "U1") (pin "19") (pinfunction "PVCC_19") (pintype "passive"))
      (node (ref "U1") (pin "31") (pinfunction "PVCC_31") (pintype "passive"))
      (node (ref "U1") (pin "32") (pinfunction "PVCC_32") (pintype "passive"))
      (node (ref "V1") (pin "1") (pinfunction "VIN_1") (pintype "passive"))
    )
    (net (code "48") (name "VCC5") (class "Default")
      (node (ref "C29") (pin "2") (pinfunction "2_2") (pintype "passive"))
      (node (ref "D18") (pin "1") (pinfunction "A_1") (pintype "passive"))
      (node (ref "D19") (pin "A") (pinfunction "A_A") (pintype "passive"))
      (node (ref "E4") (pin "1") (pinfunction "A_1") (pintype "passive"))
      (node (ref "IC1") (pin "8") (pinfunction "V+_8") (pintype "power_in"))
      (node (ref "Q1") (pin "3") (pinfunction "C_3") (pintype "passive"))
      (node (ref "R14") (pin "1") (pinfunction "1_1") (pintype "passive"))
      (node (ref "U2") (pin "3") (pinfunction "VCC_3") (pintype "passive"))
      (node (ref "USB1") (pin "1") (pinfunction "+5V_1") (pintype "passive"))
      (node (ref "V1") (pin "3") (pinfunction "VOUT_3") (pintype "passive"))
    )
    (net (code "49") (name "unconnected-(CON1-Pad3)") (class "Default")
      (node (ref "CON1") (pin "3") (pinfunction "3_3") (pintype "passive"))
    )
    (net (code "50") (name "unconnected-(U1-SYNC-Pad16)") (class "Default")
      (node (ref "U1") (pin "16") (pinfunction "SYNC_16") (pintype "passive+no_connect"))
    )
    (net (code "51") (name "unconnected-(USB1-D+-Pad3)") (class "Default")
      (node (ref "USB1") (pin "3") (pinfunction "D+_3") (pintype "passive"))
    )
    (net (code "52") (name "unconnected-(USB1-D--Pad2)") (class "Default")
      (node (ref "USB1") (pin "2") (pinfunction "D-_2") (pintype "passive"))
    )
    (net (code "53") (name "unconnected-(USB1-ID-Pad4)") (class "Default")
      (node (ref "USB1") (pin "4") (pinfunction "ID_4") (pintype "passive"))
    )
  )
)
